# BatteryPCB2989.net
KiCad netlist of a schematic drawn in EAGLE
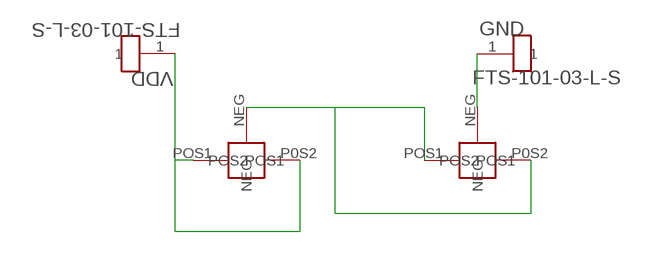
[diagram p0: schematic, sheet 1]

(export (version "E")
  (design (tool "Eeschema 10.0.6"))
  (components
    (comp (ref "GND")
      (value "FTS-101-03-L-S")
      (footprint "eagle-import:SAMTEC_FTS-101-03-S")
      (libsource (lib "eagle-import") (part "FTS-101-03-L-S"))
    )
    (comp (ref "U$1")
      (value "2989NOHOLE")
      (footprint "eagle-import:2989NOHOLE")
      (libsource (lib "eagle-import") (part "2989NOHOLE"))
    )
    (comp (ref "U$2")
      (value "2989NOHOLE")
      (footprint "eagle-import:2989NOHOLE")
      (libsource (lib "eagle-import") (part "2989NOHOLE"))
    )
    (comp (ref "VDD")
      (value "FTS-101-03-L-S")
      (footprint "eagle-import:SAMTEC_FTS-101-03-S")
      (libsource (lib "eagle-import") (part "FTS-101-03-L-S"))
    )
  )
  (nets
    (net (code "1") (name "Net-(GND-Pad1)") (class "Default")
      (node (ref "GND") (pin "1") (pinfunction "1_1") (pintype "passive"))
      (node (ref "U$2") (pin "NEG") (pinfunction "NEG_NEG") (pintype "bidirectional"))
    )
    (net (code "2") (name "Net-(U$1-POS2)") (class "Default")
      (node (ref "U$1") (pin "P0S2") (pinfunction "POS2_P0S2") (pintype "bidirectional"))
      (node (ref "U$1") (pin "POS1") (pinfunction "POS1_POS1") (pintype "bidirectional"))
      (node (ref "VDD") (pin "1") (pinfunction "1_1") (pintype "passive"))
    )
    (net (code "3") (name "Net-(U$2-POS2)") (class "Default")
      (node (ref "U$1") (pin "NEG") (pinfunction "NEG_NEG") (pintype "bidirectional"))
      (node (ref "U$2") (pin "P0S2") (pinfunction "POS2_P0S2") (pintype "bidirectional"))
      (node (ref "U$2") (pin "POS1") (pinfunction "POS1_POS1") (pintype "bidirectional"))
    )
  )
)
